# DVI_Pmod.net
KiCad netlist of a schematic drawn in EAGLE
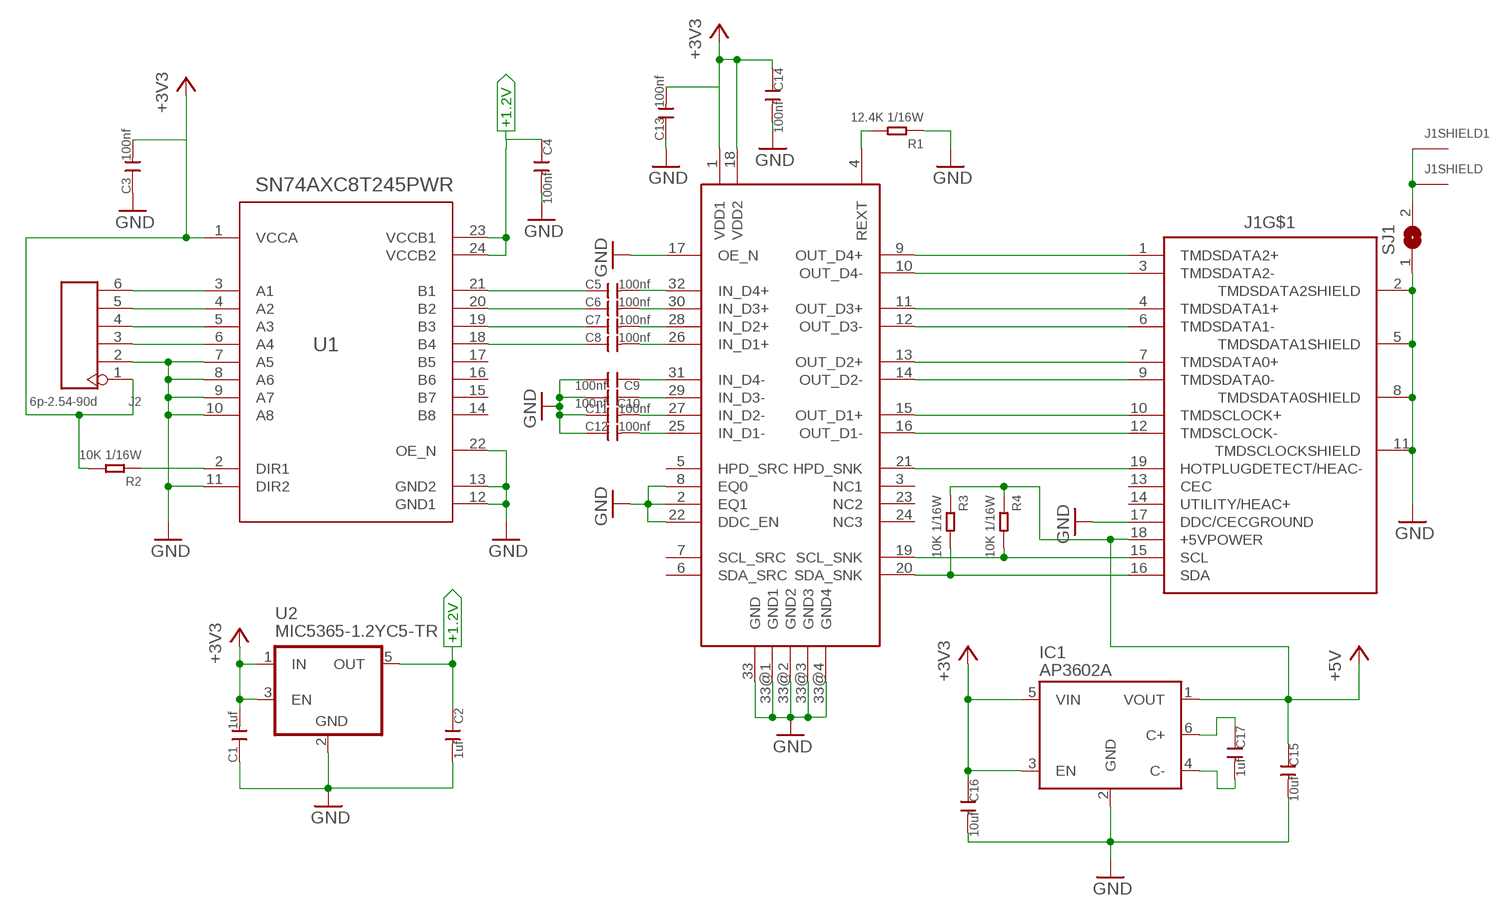
[diagram p0: schematic, sheet 1]

(export (version "E")
  (design (tool "Eeschema 10.0.6"))
  (components
    (comp (ref "C1")
      (value "1uf")
      (footprint "eagle-import:C0402")
      (fields (field (name "MPN") "CC0402KRX5R6BB105"))
      (libsource (lib "eagle-import") (part "CERAMIC-1UF-10V-10%-X5R(0402)"))
    )
    (comp (ref "C2")
      (value "1uf")
      (footprint "eagle-import:C0402")
      (fields (field (name "MPN") "CC0402KRX5R6BB105"))
      (libsource (lib "eagle-import") (part "CERAMIC-1UF-10V-10%-X5R(0402)"))
    )
    (comp (ref "C3")
      (value "100nf")
      (footprint "eagle-import:C0402")
      (fields (field (name "MPN") "CC0402KRX7R8BB104"))
      (libsource (lib "eagle-import") (part "CERAMIC-100NF-25V-10%-X7R(0402)"))
    )
    (comp (ref "C4")
      (value "100nf")
      (footprint "eagle-import:C0402")
      (fields (field (name "MPN") "CC0402KRX7R8BB104"))
      (libsource (lib "eagle-import") (part "CERAMIC-100NF-25V-10%-X7R(0402)"))
    )
    (comp (ref "C5")
      (value "100nf")
      (footprint "eagle-import:C0402")
      (fields (field (name "MPN") "CC0402KRX7R8BB104"))
      (libsource (lib "eagle-import") (part "CERAMIC-100NF-25V-10%-X7R(0402)"))
    )
    (comp (ref "C6")
      (value "100nf")
      (footprint "eagle-import:C0402")
      (fields (field (name "MPN") "CC0402KRX7R8BB104"))
      (libsource (lib "eagle-import") (part "CERAMIC-100NF-25V-10%-X7R(0402)"))
    )
    (comp (ref "C7")
      (value "100nf")
      (footprint "eagle-import:C0402")
      (fields (field (name "MPN") "CC0402KRX7R8BB104"))
      (libsource (lib "eagle-import") (part "CERAMIC-100NF-25V-10%-X7R(0402)"))
    )
    (comp (ref "C8")
      (value "100nf")
      (footprint "eagle-import:C0402")
      (fields (field (name "MPN") "CC0402KRX7R8BB104"))
      (libsource (lib "eagle-import") (part "CERAMIC-100NF-25V-10%-X7R(0402)"))
    )
    (comp (ref "C9")
      (value "100nf")
      (footprint "eagle-import:C0402")
      (fields (field (name "MPN") "CC0402KRX7R8BB104"))
      (libsource (lib "eagle-import") (part "CERAMIC-100NF-25V-10%-X7R(0402)"))
    )
    (comp (ref "C10")
      (value "100nf")
      (footprint "eagle-import:C0402")
      (fields (field (name "MPN") "CC0402KRX7R8BB104"))
      (libsource (lib "eagle-import") (part "CERAMIC-100NF-25V-10%-X7R(0402)"))
    )
    (comp (ref "C11")
      (value "100nf")
      (footprint "eagle-import:C0402")
      (fields (field (name "MPN") "CC0402KRX7R8BB104"))
      (libsource (lib "eagle-import") (part "CERAMIC-100NF-25V-10%-X7R(0402)"))
    )
    (comp (ref "C12")
      (value "100nf")
      (footprint "eagle-import:C0402")
      (fields (field (name "MPN") "CC0402KRX7R8BB104"))
      (libsource (lib "eagle-import") (part "CERAMIC-100NF-25V-10%-X7R(0402)"))
    )
    (comp (ref "C13")
      (value "100nf")
      (footprint "eagle-import:C0402")
      (fields (field (name "MPN") "CC0402KRX7R8BB104"))
      (libsource (lib "eagle-import") (part "CERAMIC-100NF-25V-10%-X7R(0402)"))
    )
    (comp (ref "C14")
      (value "100nf")
      (footprint "eagle-import:C0402")
      (fields (field (name "MPN") "CC0402KRX7R8BB104"))
      (libsource (lib "eagle-import") (part "CERAMIC-100NF-25V-10%-X7R(0402)"))
    )
    (comp (ref "C15")
      (value "10uf")
      (footprint "eagle-import:C0805")
      (fields (field (name "MPN") "CC0805KKX5R8BB106"))
      (libsource (lib "eagle-import") (part "CERAMIC-10UF-25V-10%-X5R(0805)"))
    )
    (comp (ref "C16")
      (value "10uf")
      (footprint "eagle-import:C0603")
      (fields (field (name "MPN") "CC0603KRX5R6BB106"))
      (libsource (lib "eagle-import") (part "CERAMIC-10UF-10V-10%-X5R(0603)"))
    )
    (comp (ref "C17")
      (value "1uf")
      (footprint "eagle-import:C0603")
      (fields (field (name "MPN") "CC0603KRX7R8BB105"))
      (libsource (lib "eagle-import") (part "CERAMIC-1UF-25V-10%-X7R(0603)"))
    )
    (comp (ref "IC1")
      (value "AP3602A")
      (footprint "eagle-import:SOT23-6")
      (libsource (lib "eagle-import") (part "REG710XX-5.0"))
    )
    (comp (ref "J1")
      (value "685119134923")
      (footprint "eagle-import:685119134923")
      (libsource (lib "eagle-import") (part "685119134923"))
    )
    (comp (ref "J2")
      (value "6p-2.54-90d")
      (footprint "eagle-import:H6-2.54-90D-MALE")
      (libsource (lib "eagle-import") (part "DIP-BLACK-SHORT-MALE-HEADER-R/A(6P-2.54-90D)"))
    )
    (comp (ref "R1")
      (value "12.4K 1/16W")
      (footprint "eagle-import:R0402")
      (fields (field (name "MPN") "RC0402FR-0710KL"))
      (libsource (lib "eagle-import") (part "SMD-RES-10K-1%-1/16W(0402)"))
    )
    (comp (ref "R2")
      (value "10K 1/16W")
      (footprint "eagle-import:R0402")
      (fields (field (name "MPN") "RC0402FR-0710KL"))
      (libsource (lib "eagle-import") (part "SMD-RES-10K-1%-1/16W(0402)"))
    )
    (comp (ref "R3")
      (value "10K 1/16W")
      (footprint "eagle-import:R0402")
      (fields (field (name "MPN") "RC0402FR-0710KL"))
      (libsource (lib "eagle-import") (part "SMD-RES-10K-1%-1/16W(0402)"))
    )
    (comp (ref "R4")
      (value "10K 1/16W")
      (footprint "eagle-import:R0402")
      (fields (field (name "MPN") "RC0402FR-0710KL"))
      (libsource (lib "eagle-import") (part "SMD-RES-10K-1%-1/16W(0402)"))
    )
    (comp (ref "SJ1") (value "SJ") (footprint "eagle-import:SJ") (libsource (lib "eagle-import") (part "SJ")))
    (comp (ref "U$1")
      (value "PTN3366")
      (footprint "eagle-import:SOT617-3")
      (libsource (lib "eagle-import") (part "PTN3366"))
    )
    (comp (ref "U1")
      (value "SN74AXC8T245PWR")
      (footprint "eagle-import:SOP65P640X120-24N")
      (libsource (lib "eagle-import") (part "SN74AXC8T245PWR"))
    )
    (comp (ref "U2")
      (value "MIC5365-1.2YC5-TR")
      (footprint "eagle-import:SC70-5")
      (libsource (lib "eagle-import") (part "MIC5365/6C5"))
    )
  )
  (nets
    (net (code "1") (name "+1.2V") (class "Default")
      (node (ref "C2") (pin "1") (pinfunction "1_1") (pintype "passive"))
      (node (ref "C4") (pin "1") (pinfunction "1_1") (pintype "passive"))
      (node (ref "U1") (pin "23") (pinfunction "VCCB1_23") (pintype "power_in"))
      (node (ref "U1") (pin "24") (pinfunction "VCCB2_24") (pintype "power_in"))
      (node (ref "U2") (pin "5") (pinfunction "OUT_5") (pintype "passive"))
    )
    (net (code "2") (name "+3V3") (class "Default")
      (node (ref "C1") (pin "2") (pinfunction "2_2") (pintype "passive"))
      (node (ref "C13") (pin "2") (pinfunction "2_2") (pintype "passive"))
      (node (ref "C14") (pin "1") (pinfunction "1_1") (pintype "passive"))
      (node (ref "C16") (pin "1") (pinfunction "1_1") (pintype "passive"))
      (node (ref "C3") (pin "2") (pinfunction "2_2") (pintype "passive"))
      (node (ref "IC1") (pin "3") (pinfunction "EN_3") (pintype "passive"))
      (node (ref "IC1") (pin "5") (pinfunction "VIN_5") (pintype "power_in"))
      (node (ref "J2") (pin "1") (pinfunction "1_1") (pintype "bidirectional"))
      (node (ref "R2") (pin "2") (pinfunction "2_2") (pintype "passive"))
      (node (ref "U$1") (pin "1") (pinfunction "VDD1_1") (pintype "power_in"))
      (node (ref "U$1") (pin "18") (pinfunction "VDD2_18") (pintype "power_in"))
      (node (ref "U1") (pin "1") (pinfunction "VCCA_1") (pintype "power_in"))
      (node (ref "U2") (pin "1") (pinfunction "IN_1") (pintype "input"))
      (node (ref "U2") (pin "3") (pinfunction "EN_3") (pintype "input"))
    )
    (net (code "3") (name "+5V") (class "Default")
      (node (ref "C15") (pin "1") (pinfunction "1_1") (pintype "passive"))
      (node (ref "IC1") (pin "1") (pinfunction "VOUT_1") (pintype "power_in"))
      (node (ref "J1") (pin "18") (pinfunction "+5VPOWER_18") (pintype "bidirectional"))
      (node (ref "R3") (pin "1") (pinfunction "1_1") (pintype "passive"))
      (node (ref "R4") (pin "1") (pinfunction "1_1") (pintype "passive"))
    )
    (net (code "4") (name "GND") (class "Default")
      (node (ref "C1") (pin "1") (pinfunction "1_1") (pintype "passive"))
      (node (ref "C10") (pin "2") (pinfunction "2_2") (pintype "passive"))
      (node (ref "C11") (pin "1") (pinfunction "1_1") (pintype "passive"))
      (node (ref "C12") (pin "1") (pinfunction "1_1") (pintype "passive"))
      (node (ref "C13") (pin "1") (pinfunction "1_1") (pintype "passive"))
      (node (ref "C14") (pin "2") (pinfunction "2_2") (pintype "passive"))
      (node (ref "C15") (pin "2") (pinfunction "2_2") (pintype "passive"))
      (node (ref "C16") (pin "2") (pinfunction "2_2") (pintype "passive"))
      (node (ref "C2") (pin "2") (pinfunction "2_2") (pintype "passive"))
      (node (ref "C3") (pin "1") (pinfunction "1_1") (pintype "passive"))
      (node (ref "C4") (pin "2") (pinfunction "2_2") (pintype "passive"))
      (node (ref "C9") (pin "2") (pinfunction "2_2") (pintype "passive"))
      (node (ref "IC1") (pin "2") (pinfunction "GND_2") (pintype "power_in"))
      (node (ref "J1") (pin "11") (pinfunction "TMDSCLOCKSHIELD_11") (pintype "bidirectional"))
      (node (ref "J1") (pin "17") (pinfunction "DDC/CECGROUND_17") (pintype "bidirectional"))
      (node (ref "J1") (pin "2") (pinfunction "TMDSDATA2SHIELD_2") (pintype "bidirectional"))
      (node (ref "J1") (pin "5") (pinfunction "TMDSDATA1SHIELD_5") (pintype "bidirectional"))
      (node (ref "J1") (pin "8") (pinfunction "TMDSDATA0SHIELD_8") (pintype "bidirectional"))
      (node (ref "J2") (pin "2") (pinfunction "2_2") (pintype "bidirectional"))
      (node (ref "R1") (pin "1") (pinfunction "1_1") (pintype "passive"))
      (node (ref "SJ1") (pin "1") (pinfunction "1_1") (pintype "passive"))
      (node (ref "U$1") (pin "17") (pinfunction "OE_N_17") (pintype "input"))
      (node (ref "U$1") (pin "2") (pinfunction "EQ1_2") (pintype "input"))
      (node (ref "U$1") (pin "22") (pinfunction "DDC_EN_22") (pintype "input"))
      (node (ref "U$1") (pin "33") (pinfunction "GND_33") (pintype "power_in"))
      (node (ref "U$1") (pin "33@1") (pinfunction "GND1_33@1") (pintype "power_in"))
      (node (ref "U$1") (pin "33@2") (pinfunction "GND2_33@2") (pintype "power_in"))
      (node (ref "U$1") (pin "33@3") (pinfunction "GND3_33@3") (pintype "power_in"))
      (node (ref "U$1") (pin "33@4") (pinfunction "GND4_33@4") (pintype "power_in"))
      (node (ref "U$1") (pin "8") (pinfunction "EQ0_8") (pintype "input"))
      (node (ref "U1") (pin "10") (pinfunction "A8_10") (pintype "bidirectional"))
      (node (ref "U1") (pin "11") (pinfunction "DIR2_11") (pintype "input"))
      (node (ref "U1") (pin "12") (pinfunction "GND1_12") (pintype "power_in"))
      (node (ref "U1") (pin "13") (pinfunction "GND2_13") (pintype "power_in"))
      (node (ref "U1") (pin "22") (pinfunction "OE_N_22") (pintype "input"))
      (node (ref "U1") (pin "7") (pinfunction "A5_7") (pintype "bidirectional"))
      (node (ref "U1") (pin "8") (pinfunction "A6_8") (pintype "bidirectional"))
      (node (ref "U1") (pin "9") (pinfunction "A7_9") (pintype "bidirectional"))
      (node (ref "U2") (pin "2") (pinfunction "GND_2") (pintype "power_in"))
    )
    (net (code "5") (name "Net-(IC1-C+)") (class "Default")
      (node (ref "C17") (pin "1") (pinfunction "1_1") (pintype "passive"))
      (node (ref "IC1") (pin "6") (pinfunction "C+_6") (pintype "passive"))
    )
    (net (code "6") (name "Net-(IC1-C-)") (class "Default")
      (node (ref "C17") (pin "2") (pinfunction "2_2") (pintype "passive"))
      (node (ref "IC1") (pin "4") (pinfunction "C-_4") (pintype "passive"))
    )
    (net (code "7") (name "Net-(J1A-HOTPLUGDETECT{slash}HEAC-)") (class "Default")
      (node (ref "J1") (pin "19") (pinfunction "HOTPLUGDETECT/HEAC-_19") (pintype "bidirectional"))
      (node (ref "U$1") (pin "21") (pinfunction "HPD_SNK_21") (pintype "input"))
    )
    (net (code "8") (name "Net-(J1A-SCL)") (class "Default")
      (node (ref "J1") (pin "15") (pinfunction "SCL_15") (pintype "bidirectional"))
      (node (ref "R4") (pin "2") (pinfunction "2_2") (pintype "passive"))
      (node (ref "U$1") (pin "19") (pinfunction "SCL_SNK_19") (pintype "bidirectional"))
    )
    (net (code "9") (name "Net-(J1A-SDA)") (class "Default")
      (node (ref "J1") (pin "16") (pinfunction "SDA_16") (pintype "bidirectional"))
      (node (ref "R3") (pin "2") (pinfunction "2_2") (pintype "passive"))
      (node (ref "U$1") (pin "20") (pinfunction "SDA_SNK_20") (pintype "bidirectional"))
    )
    (net (code "10") (name "Net-(J1A-TMDSCLOCK+)") (class "Default")
      (node (ref "J1") (pin "10") (pinfunction "TMDSCLOCK+_10") (pintype "bidirectional"))
      (node (ref "U$1") (pin "15") (pinfunction "OUT_D1+_15") (pintype "output"))
    )
    (net (code "11") (name "Net-(J1A-TMDSCLOCK-)") (class "Default")
      (node (ref "J1") (pin "12") (pinfunction "TMDSCLOCK-_12") (pintype "bidirectional"))
      (node (ref "U$1") (pin "16") (pinfunction "OUT_D1-_16") (pintype "output"))
    )
    (net (code "12") (name "Net-(J1A-TMDSDATA0+)") (class "Default")
      (node (ref "J1") (pin "7") (pinfunction "TMDSDATA0+_7") (pintype "bidirectional"))
      (node (ref "U$1") (pin "13") (pinfunction "OUT_D2+_13") (pintype "output"))
    )
    (net (code "13") (name "Net-(J1A-TMDSDATA0-)") (class "Default")
      (node (ref "J1") (pin "9") (pinfunction "TMDSDATA0-_9") (pintype "bidirectional"))
      (node (ref "U$1") (pin "14") (pinfunction "OUT_D2-_14") (pintype "output"))
    )
    (net (code "14") (name "Net-(J1A-TMDSDATA1+)") (class "Default")
      (node (ref "J1") (pin "4") (pinfunction "TMDSDATA1+_4") (pintype "bidirectional"))
      (node (ref "U$1") (pin "11") (pinfunction "OUT_D3+_11") (pintype "output"))
    )
    (net (code "15") (name "Net-(J1A-TMDSDATA1-)") (class "Default")
      (node (ref "J1") (pin "6") (pinfunction "TMDSDATA1-_6") (pintype "bidirectional"))
      (node (ref "U$1") (pin "12") (pinfunction "OUT_D3-_12") (pintype "output"))
    )
    (net (code "16") (name "Net-(J1A-TMDSDATA2+)") (class "Default")
      (node (ref "J1") (pin "1") (pinfunction "TMDSDATA2+_1") (pintype "bidirectional"))
      (node (ref "U$1") (pin "9") (pinfunction "OUT_D4+_9") (pintype "output"))
    )
    (net (code "17") (name "Net-(J1A-TMDSDATA2-)") (class "Default")
      (node (ref "J1") (pin "3") (pinfunction "TMDSDATA2-_3") (pintype "bidirectional"))
      (node (ref "U$1") (pin "10") (pinfunction "OUT_D4-_10") (pintype "output"))
    )
    (net (code "18") (name "Net-(J1B-SHIELD)") (class "Default")
      (node (ref "J1") (pin "SHELL") (pinfunction "SHIELD_SHELL") (pintype "passive"))
      (node (ref "J1") (pin "SHELL1") (pinfunction "SHIELD_SHELL1") (pintype "passive"))
      (node (ref "SJ1") (pin "2") (pinfunction "2_2") (pintype "passive"))
    )
    (net (code "19") (name "Net-(U$1-IN_D1+)") (class "Default")
      (node (ref "C8") (pin "2") (pinfunction "2_2") (pintype "passive"))
      (node (ref "U$1") (pin "26") (pinfunction "IN_D1+_26") (pintype "input"))
    )
    (net (code "20") (name "Net-(U$1-IN_D1-)") (class "Default")
      (node (ref "C12") (pin "2") (pinfunction "2_2") (pintype "passive"))
      (node (ref "U$1") (pin "25") (pinfunction "IN_D1-_25") (pintype "input"))
    )
    (net (code "21") (name "Net-(U$1-IN_D2+)") (class "Default")
      (node (ref "C7") (pin "2") (pinfunction "2_2") (pintype "passive"))
      (node (ref "U$1") (pin "28") (pinfunction "IN_D2+_28") (pintype "input"))
    )
    (net (code "22") (name "Net-(U$1-IN_D2-)") (class "Default")
      (node (ref "C11") (pin "2") (pinfunction "2_2") (pintype "passive"))
      (node (ref "U$1") (pin "27") (pinfunction "IN_D2-_27") (pintype "input"))
    )
    (net (code "23") (name "Net-(U$1-IN_D3+)") (class "Default")
      (node (ref "C6") (pin "2") (pinfunction "2_2") (pintype "passive"))
      (node (ref "U$1") (pin "30") (pinfunction "IN_D3+_30") (pintype "input"))
    )
    (net (code "24") (name "Net-(U$1-IN_D3-)") (class "Default")
      (node (ref "C10") (pin "1") (pinfunction "1_1") (pintype "passive"))
      (node (ref "U$1") (pin "29") (pinfunction "IN_D3-_29") (pintype "input"))
    )
    (net (code "25") (name "Net-(U$1-IN_D4+)") (class "Default")
      (node (ref "C5") (pin "2") (pinfunction "2_2") (pintype "passive"))
      (node (ref "U$1") (pin "32") (pinfunction "IN_D4+_32") (pintype "input"))
    )
    (net (code "26") (name "Net-(U$1-IN_D4-)") (class "Default")
      (node (ref "C9") (pin "1") (pinfunction "1_1") (pintype "passive"))
      (node (ref "U$1") (pin "31") (pinfunction "IN_D4-_31") (pintype "input"))
    )
    (net (code "27") (name "Net-(U$1-REXT)") (class "Default")
      (node (ref "R1") (pin "2") (pinfunction "2_2") (pintype "passive"))
      (node (ref "U$1") (pin "4") (pinfunction "REXT_4") (pintype "bidirectional"))
    )
    (net (code "28") (name "Net-(U1-A1)") (class "Default")
      (node (ref "J2") (pin "6") (pinfunction "6_6") (pintype "bidirectional"))
      (node (ref "U1") (pin "3") (pinfunction "A1_3") (pintype "bidirectional"))
    )
    (net (code "29") (name "Net-(U1-A2)") (class "Default")
      (node (ref "J2") (pin "5") (pinfunction "5_5") (pintype "bidirectional"))
      (node (ref "U1") (pin "4") (pinfunction "A2_4") (pintype "bidirectional"))
    )
    (net (code "30") (name "Net-(U1-A3)") (class "Default")
      (node (ref "J2") (pin "4") (pinfunction "4_4") (pintype "bidirectional"))
      (node (ref "U1") (pin "5") (pinfunction "A3_5") (pintype "bidirectional"))
    )
    (net (code "31") (name "Net-(U1-A4)") (class "Default")
      (node (ref "J2") (pin "3") (pinfunction "3_3") (pintype "bidirectional"))
      (node (ref "U1") (pin "6") (pinfunction "A4_6") (pintype "bidirectional"))
    )
    (net (code "32") (name "Net-(U1-B1)") (class "Default")
      (node (ref "C5") (pin "1") (pinfunction "1_1") (pintype "passive"))
      (node (ref "U1") (pin "21") (pinfunction "B1_21") (pintype "bidirectional"))
    )
    (net (code "33") (name "Net-(U1-B2)") (class "Default")
      (node (ref "C6") (pin "1") (pinfunction "1_1") (pintype "passive"))
      (node (ref "U1") (pin "20") (pinfunction "B2_20") (pintype "bidirectional"))
    )
    (net (code "34") (name "Net-(U1-B3)") (class "Default")
      (node (ref "C7") (pin "1") (pinfunction "1_1") (pintype "passive"))
      (node (ref "U1") (pin "19") (pinfunction "B3_19") (pintype "bidirectional"))
    )
    (net (code "35") (name "Net-(U1-B4)") (class "Default")
      (node (ref "C8") (pin "1") (pinfunction "1_1") (pintype "passive"))
      (node (ref "U1") (pin "18") (pinfunction "B4_18") (pintype "bidirectional"))
    )
    (net (code "36") (name "Net-(U1-DIR1)") (class "Default")
      (node (ref "R2") (pin "1") (pinfunction "1_1") (pintype "passive"))
      (node (ref "U1") (pin "2") (pinfunction "DIR1_2") (pintype "input"))
    )
    (net (code "37") (name "unconnected-(J1A-CEC-Pad13)") (class "Default")
      (node (ref "J1") (pin "13") (pinfunction "CEC_13") (pintype "bidirectional"))
    )
    (net (code "38") (name "unconnected-(J1A-UTILITY{slash}HEAC+-Pad14)") (class "Default")
      (node (ref "J1") (pin "14") (pinfunction "UTILITY/HEAC+_14") (pintype "bidirectional"))
    )
    (net (code "39") (name "unconnected-(U$1-HPD_SRC-Pad5)") (class "Default")
      (node (ref "U$1") (pin "5") (pinfunction "HPD_SRC_5") (pintype "output"))
    )
    (net (code "40") (name "unconnected-(U$1-NC1-Pad3)") (class "Default")
      (node (ref "U$1") (pin "3") (pinfunction "NC1_3") (pintype "no_connect"))
    )
    (net (code "41") (name "unconnected-(U$1-NC2-Pad23)") (class "Default")
      (node (ref "U$1") (pin "23") (pinfunction "NC2_23") (pintype "no_connect"))
    )
    (net (code "42") (name "unconnected-(U$1-NC3-Pad24)") (class "Default")
      (node (ref "U$1") (pin "24") (pinfunction "NC3_24") (pintype "no_connect"))
    )
    (net (code "43") (name "unconnected-(U$1-SCL_SRC-Pad7)") (class "Default")
      (node (ref "U$1") (pin "7") (pinfunction "SCL_SRC_7") (pintype "bidirectional"))
    )
    (net (code "44") (name "unconnected-(U$1-SDA_SRC-Pad6)") (class "Default")
      (node (ref "U$1") (pin "6") (pinfunction "SDA_SRC_6") (pintype "bidirectional"))
    )
    (net (code "45") (name "unconnected-(U1-B5-Pad17)") (class "Default")
      (node (ref "U1") (pin "17") (pinfunction "B5_17") (pintype "bidirectional"))
    )
    (net (code "46") (name "unconnected-(U1-B6-Pad16)") (class "Default")
      (node (ref "U1") (pin "16") (pinfunction "B6_16") (pintype "bidirectional"))
    )
    (net (code "47") (name "unconnected-(U1-B7-Pad15)") (class "Default")
      (node (ref "U1") (pin "15") (pinfunction "B7_15") (pintype "bidirectional"))
    )
    (net (code "48") (name "unconnected-(U1-B8-Pad14)") (class "Default")
      (node (ref "U1") (pin "14") (pinfunction "B8_14") (pintype "bidirectional"))
    )
  )
)
